# MCU.net
KiCad netlist of a schematic drawn in Altium Designer
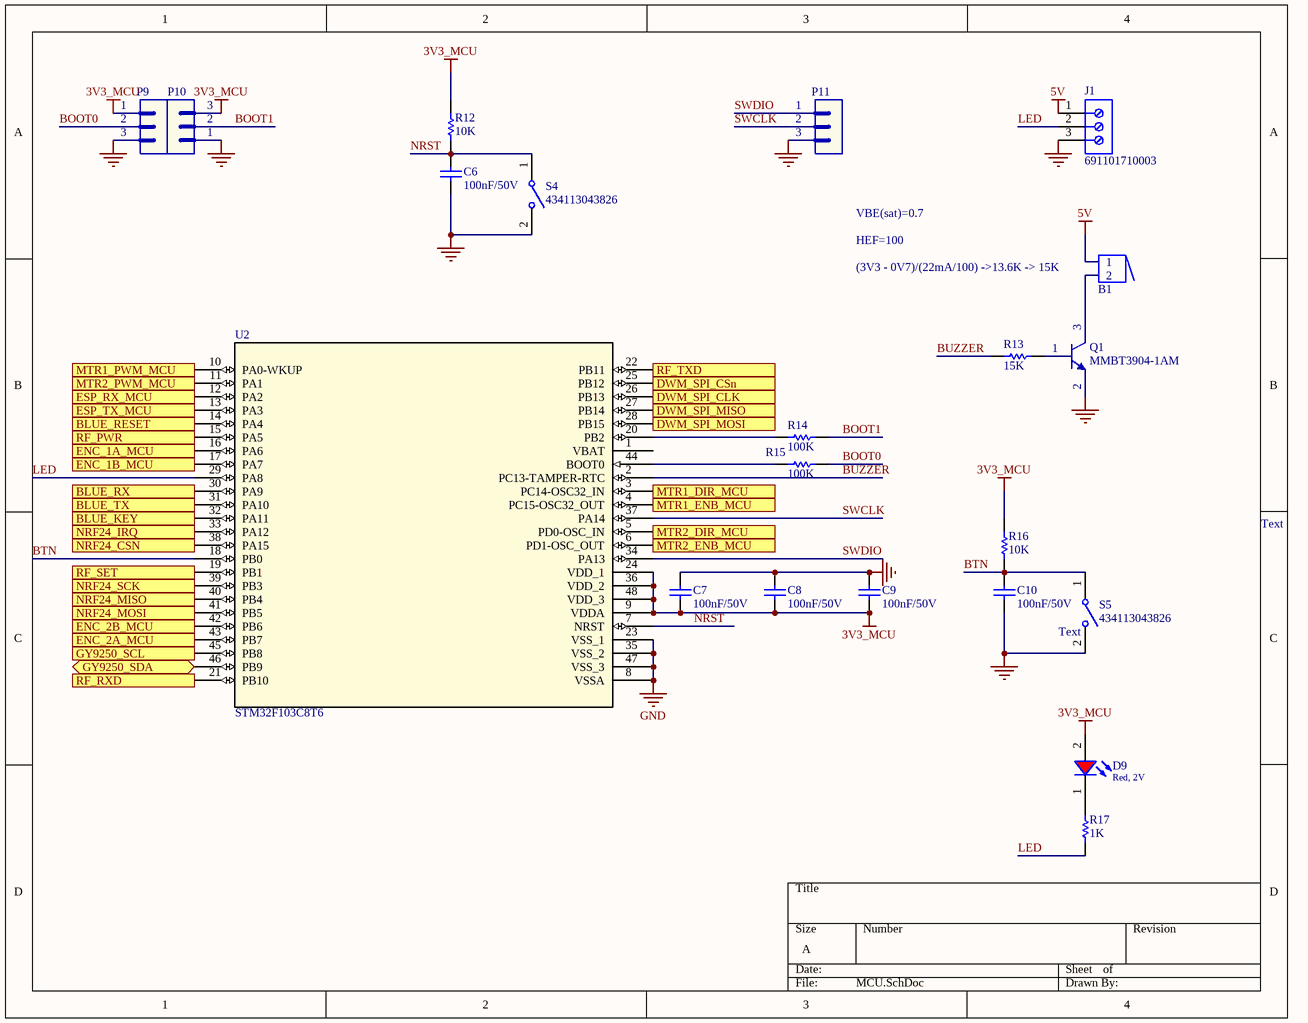
[diagram p0: MCU.SchDoc]

(export (version "E")
  (design (tool "Eeschema 10.0.6"))
  (components
    (comp (ref "B1") (value "Buzzer") (footprint "BUZZER") (libsource (lib "PIF_C16_2_lib") (part "Buzzer")))
    (comp (ref "C6")
      (value "100nF/50V")
      (footprint "CAP-SM-0805")
      (description "CAP CER 0.1UF 50V Y5V 0805")
      (fields
        (field (name "MANUFACTURER") "Samsung Electro-Mechanics")
        (field (name "MANUFACTURER PART NUMBER") "CL21F104ZBCNNNC")
      )
      (libsource (lib "Capacitor") (part "Cap-100nF-50V-0805"))
    )
    (comp (ref "C7")
      (value "100nF/50V")
      (footprint "CAP-SM-0805")
      (description "CAP CER 0.1UF 50V Y5V 0805")
      (fields
        (field (name "MANUFACTURER") "Samsung Electro-Mechanics")
        (field (name "MANUFACTURER PART NUMBER") "CL21F104ZBCNNNC")
      )
      (libsource (lib "Capacitor") (part "Cap-100nF-50V-0805"))
    )
    (comp (ref "C8")
      (value "100nF/50V")
      (footprint "CAP-SM-0805")
      (description "CAP CER 0.1UF 50V Y5V 0805")
      (fields
        (field (name "MANUFACTURER") "Samsung Electro-Mechanics")
        (field (name "MANUFACTURER PART NUMBER") "CL21F104ZBCNNNC")
      )
      (libsource (lib "Capacitor") (part "Cap-100nF-50V-0805"))
    )
    (comp (ref "C9")
      (value "100nF/50V")
      (footprint "CAP-SM-0805")
      (description "CAP CER 0.1UF 50V Y5V 0805")
      (fields
        (field (name "MANUFACTURER") "Samsung Electro-Mechanics")
        (field (name "MANUFACTURER PART NUMBER") "CL21F104ZBCNNNC")
      )
      (libsource (lib "Capacitor") (part "Cap-100nF-50V-0805"))
    )
    (comp (ref "C10")
      (value "100nF/50V")
      (footprint "CAP-SM-0805")
      (description "CAP CER 0.1UF 50V Y5V 0805")
      (fields
        (field (name "MANUFACTURER") "Samsung Electro-Mechanics")
        (field (name "MANUFACTURER PART NUMBER") "CL21F104ZBCNNNC")
      )
      (libsource (lib "Capacitor") (part "Cap-100nF-50V-0805"))
    )
    (comp (ref "D9")
      (value "Red, 2V")
      (footprint "WL-SMCW_0805")
      (description "WL-SMCW SMT Mono-color Chip LED Waterclear, size 0805, Red, 2V, 140deg")
      (fields (field (name "PART NUMBER") "150080RS75000") (field (name "PUBLISHER") "Wurth Elektronik"))
      (libsource (lib "150080BS75000_Altium_WL-SMCW_rev20a") (part "150080RS75000"))
    )
    (comp (ref "J1")
      (value "691101710003")
      (footprint "691101710003")
      (description "WR-TBL Serie 101 Horizontal Entry Modular, Pressure Clamp, pitch 5mm, 3p")
      (fields (field (name "PUBLISHER") "Wurth Elektronik"))
      (libsource (lib "691101710002_Altium_WR-TBL_rev19a") (part "691101710003"))
    )
    (comp (ref "P9")
      (value "~")
      (footprint "JP3")
      (description "Header, 3-Pin")
      (fields (field (name "PUBLISHER") "Altium Limited"))
      (libsource (lib "PIF_C16_2_lib") (part "Header 3"))
    )
    (comp (ref "P10")
      (value "~")
      (footprint "JP3")
      (description "Header, 3-Pin")
      (fields (field (name "PUBLISHER") "Altium Limited"))
      (libsource (lib "") (part "Header 3_1"))
    )
    (comp (ref "P11")
      (value "~")
      (footprint "JP3")
      (description "Header, 3-Pin")
      (fields (field (name "PUBLISHER") "Altium Limited"))
      (libsource (lib "PIF_C16_2_lib") (part "Header 3"))
    )
    (comp (ref "Q1")
      (value "MMBT3904-1AM")
      (footprint "SOT23_NEX")
      (libsource (lib "BJT") (part "MMBT3904-1AM"))
    )
    (comp (ref "R12")
      (value "10K")
      (footprint "Resistor:RES-SM-0805")
      (description "RES 10K OHM 1% 1/4W 0805")
      (fields
        (field (name "MANUFACTURER") "Stackpole Electronics Inc")
        (field (name "MANUFACTURER PART NUMBER") "RNCP0805FTD10K0")
      )
      (libsource (lib "Resistor") (part "Res-10k-0805"))
    )
    (comp (ref "R13")
      (value "15K")
      (footprint "Resistor:RES-SM-0805")
      (description "RES 15K OHM 1% 1/4W 0805")
      (fields
        (field (name "MANUFACTURER") "TE Connectivity Passive Product")
        (field (name "MANUFACTURER PART NUMBER") "CRGCQ0805F15K")
      )
      (libsource (lib "Resistor") (part "Res-15K-0805"))
    )
    (comp (ref "R14")
      (value "100K")
      (footprint "Resistor:RES-SM-0805")
      (description "RES 0 OHM JUMPER 0805")
      (fields
        (field (name "MANUFACTURER") "Vishay Dale")
        (field (name "MANUFACTURER PART NUMBER") "WSL080500000ZEA9")
      )
      (libsource (lib "Resistor") (part "Res-100K-0805"))
    )
    (comp (ref "R15")
      (value "100K")
      (footprint "Resistor:RES-SM-0805")
      (description "RES 0 OHM JUMPER 0805")
      (fields
        (field (name "MANUFACTURER") "Vishay Dale")
        (field (name "MANUFACTURER PART NUMBER") "WSL080500000ZEA9")
      )
      (libsource (lib "Resistor") (part "Res-100K-0805"))
    )
    (comp (ref "R16")
      (value "10K")
      (footprint "Resistor:RES-SM-0805")
      (description "RES 10K OHM 1% 1/4W 0805")
      (fields
        (field (name "MANUFACTURER") "Stackpole Electronics Inc")
        (field (name "MANUFACTURER PART NUMBER") "RNCP0805FTD10K0")
      )
      (libsource (lib "Resistor") (part "Res-10k-0805"))
    )
    (comp (ref "R17")
      (value "1K")
      (footprint "Resistor:RES-SM-0805")
      (description "RES 1K OHM 1% 1/4W 0805")
      (fields
        (field (name "MANUFACTURER") "Stackpole Electronics Inc")
        (field (name "MANUFACTURER PART NUMBER") "RNCP0805FTD1K00")
      )
      (libsource (lib "Resistor") (part "Res-1K-0805"))
    )
    (comp (ref "S4")
      (value "434113043826")
      (footprint "434113043826")
      (description "WS-TASV J-Bend SMT Tact Switch 6x3.5mm, height 4.3mm, 260gf")
      (fields (field (name "PUBLISHER") "Wurth Elektronik"))
      (libsource (lib "434113043826_Altium_WS-TASV_rev20a") (part "434113043826"))
    )
    (comp (ref "S5")
      (value "434113043826")
      (footprint "434113043826")
      (description "WS-TASV J-Bend SMT Tact Switch 6x3.5mm, height 4.3mm, 260gf")
      (fields (field (name "PUBLISHER") "Wurth Elektronik"))
      (libsource (lib "434113043826_Altium_WS-TASV_rev20a") (part "434113043826"))
    )
    (comp (ref "U2")
      (value "STM32F103C8T6")
      (footprint "LQFP-48")
      (description "No Description Available")
      (fields (field (name "COPYRIGHT") "Copyright (C) 2018 Accelerated Designs. All rights reserved"))
      (libsource (lib "Schlib1") (part "STM32F103C8T6"))
    )
  )
  (nets
    (net (code "1") (name "/BLUE_KEY") (class "Default")
      (node (ref "U2") (pin "32") (pinfunction "PA11_32") (pintype "bidirectional"))
    )
    (net (code "2") (name "/BLUE_RESET") (class "Default")
      (node (ref "U2") (pin "14") (pinfunction "PA4_14") (pintype "bidirectional"))
    )
    (net (code "3") (name "/BLUE_RX") (class "Default")
      (node (ref "U2") (pin "30") (pinfunction "PA9_30") (pintype "bidirectional"))
    )
    (net (code "4") (name "/BLUE_TX") (class "Default")
      (node (ref "U2") (pin "31") (pinfunction "PA10_31") (pintype "bidirectional"))
    )
    (net (code "5") (name "/BOOT0") (class "Default")
      (node (ref "P9") (pin "2") (pinfunction "2_2") (pintype "passive"))
      (node (ref "R15") (pin "2") (pinfunction "2_2") (pintype "passive"))
    )
    (net (code "6") (name "/BOOT1") (class "Default")
      (node (ref "P10") (pin "2") (pinfunction "2_2") (pintype "passive"))
      (node (ref "R14") (pin "2") (pinfunction "2_2") (pintype "passive"))
    )
    (net (code "7") (name "/BTN") (class "Default")
      (node (ref "C10") (pin "2") (pinfunction "2_2") (pintype "passive"))
      (node (ref "R16") (pin "2") (pinfunction "2_2") (pintype "passive"))
      (node (ref "S5") (pin "1") (pinfunction "1_1") (pintype "passive"))
      (node (ref "U2") (pin "18") (pinfunction "PB0_18") (pintype "bidirectional"))
    )
    (net (code "8") (name "/BUZZER") (class "Default")
      (node (ref "R13") (pin "1") (pinfunction "1_1") (pintype "passive"))
      (node (ref "U2") (pin "2") (pinfunction "PC13-TAMPER-RTC_2") (pintype "bidirectional"))
    )
    (net (code "9") (name "/DWM_SPI_CLK") (class "Default")
      (node (ref "U2") (pin "26") (pinfunction "PB13_26") (pintype "bidirectional"))
    )
    (net (code "10") (name "/DWM_SPI_CSn") (class "Default")
      (node (ref "U2") (pin "25") (pinfunction "PB12_25") (pintype "bidirectional"))
    )
    (net (code "11") (name "/DWM_SPI_MISO") (class "Default")
      (node (ref "U2") (pin "27") (pinfunction "PB14_27") (pintype "bidirectional"))
    )
    (net (code "12") (name "/DWM_SPI_MOSI") (class "Default")
      (node (ref "U2") (pin "28") (pinfunction "PB15_28") (pintype "bidirectional"))
    )
    (net (code "13") (name "/ENC_1A_MCU") (class "Default")
      (node (ref "U2") (pin "16") (pinfunction "PA6_16") (pintype "bidirectional"))
    )
    (net (code "14") (name "/ENC_1B_MCU") (class "Default")
      (node (ref "U2") (pin "17") (pinfunction "PA7_17") (pintype "bidirectional"))
    )
    (net (code "15") (name "/ENC_2A_MCU") (class "Default")
      (node (ref "U2") (pin "43") (pinfunction "PB7_43") (pintype "bidirectional"))
    )
    (net (code "16") (name "/ENC_2B_MCU") (class "Default")
      (node (ref "U2") (pin "42") (pinfunction "PB6_42") (pintype "bidirectional"))
    )
    (net (code "17") (name "/ESP_RX_MCU") (class "Default")
      (node (ref "U2") (pin "12") (pinfunction "PA2_12") (pintype "bidirectional"))
    )
    (net (code "18") (name "/ESP_TX_MCU") (class "Default")
      (node (ref "U2") (pin "13") (pinfunction "PA3_13") (pintype "bidirectional"))
    )
    (net (code "19") (name "/GY9250_SCL") (class "Default")
      (node (ref "U2") (pin "45") (pinfunction "PB8_45") (pintype "bidirectional"))
    )
    (net (code "20") (name "/GY9250_SDA") (class "Default")
      (node (ref "U2") (pin "46") (pinfunction "PB9_46") (pintype "bidirectional"))
    )
    (net (code "21") (name "/LED") (class "Default")
      (node (ref "J1") (pin "2") (pinfunction "2_2") (pintype "passive"))
      (node (ref "R17") (pin "1") (pinfunction "1_1") (pintype "passive"))
      (node (ref "U2") (pin "29") (pinfunction "PA8_29") (pintype "bidirectional"))
    )
    (net (code "22") (name "/MTR1_DIR_MCU") (class "Default")
      (node (ref "U2") (pin "3") (pinfunction "PC14-OSC32_IN_3") (pintype "bidirectional"))
    )
    (net (code "23") (name "/MTR1_ENB_MCU") (class "Default")
      (node (ref "U2") (pin "4") (pinfunction "PC15-OSC32_OUT_4") (pintype "bidirectional"))
    )
    (net (code "24") (name "/MTR1_PWM_MCU") (class "Default")
      (node (ref "U2") (pin "10") (pinfunction "PA0-WKUP_10") (pintype "bidirectional"))
    )
    (net (code "25") (name "/MTR2_DIR_MCU") (class "Default")
      (node (ref "U2") (pin "5") (pinfunction "PD0-OSC_IN_5") (pintype "bidirectional"))
    )
    (net (code "26") (name "/MTR2_ENB_MCU") (class "Default")
      (node (ref "U2") (pin "6") (pinfunction "PD1-OSC_OUT_6") (pintype "bidirectional"))
    )
    (net (code "27") (name "/MTR2_PWM_MCU") (class "Default")
      (node (ref "U2") (pin "11") (pinfunction "PA1_11") (pintype "bidirectional"))
    )
    (net (code "28") (name "/NRF24_CSN") (class "Default")
      (node (ref "U2") (pin "38") (pinfunction "PA15_38") (pintype "bidirectional"))
    )
    (net (code "29") (name "/NRF24_IRQ") (class "Default")
      (node (ref "U2") (pin "33") (pinfunction "PA12_33") (pintype "bidirectional"))
    )
    (net (code "30") (name "/NRF24_MISO") (class "Default")
      (node (ref "U2") (pin "40") (pinfunction "PB4_40") (pintype "bidirectional"))
    )
    (net (code "31") (name "/NRF24_MOSI") (class "Default")
      (node (ref "U2") (pin "41") (pinfunction "PB5_41") (pintype "bidirectional"))
    )
    (net (code "32") (name "/NRF24_SCK") (class "Default")
      (node (ref "U2") (pin "39") (pinfunction "PB3_39") (pintype "bidirectional"))
    )
    (net (code "33") (name "/NRST") (class "Default")
      (node (ref "C6") (pin "2") (pinfunction "2_2") (pintype "passive"))
      (node (ref "R12") (pin "2") (pinfunction "2_2") (pintype "passive"))
      (node (ref "S4") (pin "1") (pinfunction "1_1") (pintype "passive"))
      (node (ref "U2") (pin "7") (pinfunction "NRST_7") (pintype "bidirectional"))
    )
    (net (code "34") (name "/RF_PWR") (class "Default")
      (node (ref "U2") (pin "15") (pinfunction "PA5_15") (pintype "bidirectional"))
    )
    (net (code "35") (name "/RF_RXD") (class "Default")
      (node (ref "U2") (pin "21") (pinfunction "PB10_21") (pintype "bidirectional"))
    )
    (net (code "36") (name "/RF_SET") (class "Default")
      (node (ref "U2") (pin "19") (pinfunction "PB1_19") (pintype "bidirectional"))
    )
    (net (code "37") (name "/RF_TXD") (class "Default")
      (node (ref "U2") (pin "22") (pinfunction "PB11_22") (pintype "bidirectional"))
    )
    (net (code "38") (name "/SWCLK") (class "Default")
      (node (ref "P11") (pin "2") (pinfunction "2_2") (pintype "passive"))
      (node (ref "U2") (pin "37") (pinfunction "PA14_37") (pintype "bidirectional"))
    )
    (net (code "39") (name "/SWDIO") (class "Default")
      (node (ref "P11") (pin "1") (pinfunction "1_1") (pintype "passive"))
      (node (ref "U2") (pin "34") (pinfunction "PA13_34") (pintype "bidirectional"))
    )
    (net (code "40") (name "3V3_MCU") (class "Default")
      (node (ref "C7") (pin "1") (pinfunction "1_1") (pintype "passive"))
      (node (ref "C8") (pin "1") (pinfunction "1_1") (pintype "passive"))
      (node (ref "C9") (pin "1") (pinfunction "1_1") (pintype "passive"))
      (node (ref "D9") (pin "2") (pinfunction "A_2") (pintype "passive"))
      (node (ref "P10") (pin "3") (pinfunction "3_3") (pintype "passive"))
      (node (ref "P9") (pin "1") (pinfunction "1_1") (pintype "passive"))
      (node (ref "R12") (pin "1") (pinfunction "1_1") (pintype "passive"))
      (node (ref "R16") (pin "1") (pinfunction "1_1") (pintype "passive"))
      (node (ref "U2") (pin "24") (pinfunction "VDD_1_24") (pintype "power_in"))
      (node (ref "U2") (pin "36") (pinfunction "VDD_2_36") (pintype "power_in"))
      (node (ref "U2") (pin "48") (pinfunction "VDD_3_48") (pintype "power_in"))
      (node (ref "U2") (pin "9") (pinfunction "VDDA_9") (pintype "power_in"))
    )
    (net (code "41") (name "5V") (class "Default")
      (node (ref "B1") (pin "1") (pinfunction "1_1") (pintype "passive"))
      (node (ref "J1") (pin "1") (pinfunction "1_1") (pintype "passive"))
    )
    (net (code "42") (name "GND") (class "Default")
      (node (ref "C10") (pin "1") (pinfunction "1_1") (pintype "passive"))
      (node (ref "C6") (pin "1") (pinfunction "1_1") (pintype "passive"))
      (node (ref "C7") (pin "2") (pinfunction "2_2") (pintype "passive"))
      (node (ref "C8") (pin "2") (pinfunction "2_2") (pintype "passive"))
      (node (ref "C9") (pin "2") (pinfunction "2_2") (pintype "passive"))
      (node (ref "J1") (pin "3") (pinfunction "3_3") (pintype "passive"))
      (node (ref "P10") (pin "1") (pinfunction "1_1") (pintype "passive"))
      (node (ref "P11") (pin "3") (pinfunction "3_3") (pintype "passive"))
      (node (ref "P9") (pin "3") (pinfunction "3_3") (pintype "passive"))
      (node (ref "Q1") (pin "2") (pinfunction "E_2") (pintype "passive"))
      (node (ref "S4") (pin "2") (pinfunction "2_2") (pintype "passive"))
      (node (ref "S5") (pin "2") (pinfunction "2_2") (pintype "passive"))
      (node (ref "U2") (pin "23") (pinfunction "VSS_1_23") (pintype "power_in"))
      (node (ref "U2") (pin "35") (pinfunction "VSS_2_35") (pintype "power_in"))
      (node (ref "U2") (pin "47") (pinfunction "VSS_3_47") (pintype "power_in"))
      (node (ref "U2") (pin "8") (pinfunction "VSSA_8") (pintype "power_in"))
    )
    (net (code "43") (name "Net-(D9-K)") (class "Default")
      (node (ref "D9") (pin "1") (pinfunction "K_1") (pintype "passive"))
      (node (ref "R17") (pin "2") (pinfunction "2_2") (pintype "passive"))
    )
    (net (code "44") (name "Net-(Q1-B)") (class "Default")
      (node (ref "Q1") (pin "1") (pinfunction "B_1") (pintype "passive"))
      (node (ref "R13") (pin "2") (pinfunction "2_2") (pintype "passive"))
    )
    (net (code "45") (name "Net-(Q1-C)") (class "Default")
      (node (ref "B1") (pin "2") (pinfunction "2_2") (pintype "passive"))
      (node (ref "Q1") (pin "3") (pinfunction "C_3") (pintype "passive"))
    )
    (net (code "46") (name "Net-(U2-BOOT0)") (class "Default")
      (node (ref "R15") (pin "1") (pinfunction "1_1") (pintype "passive"))
      (node (ref "U2") (pin "44") (pinfunction "BOOT0_44") (pintype "input"))
    )
    (net (code "47") (name "Net-(U2-PB2)") (class "Default")
      (node (ref "R14") (pin "1") (pinfunction "1_1") (pintype "passive"))
      (node (ref "U2") (pin "20") (pinfunction "PB2_20") (pintype "bidirectional"))
    )
    (net (code "48") (name "unconnected-(U2-VBAT-Pad1)") (class "Default")
      (node (ref "U2") (pin "1") (pinfunction "VBAT_1") (pintype "power_in"))
    )
  )
)
